# Real_Time_Clock.net
KiCad netlist of a schematic drawn in Altium Designer
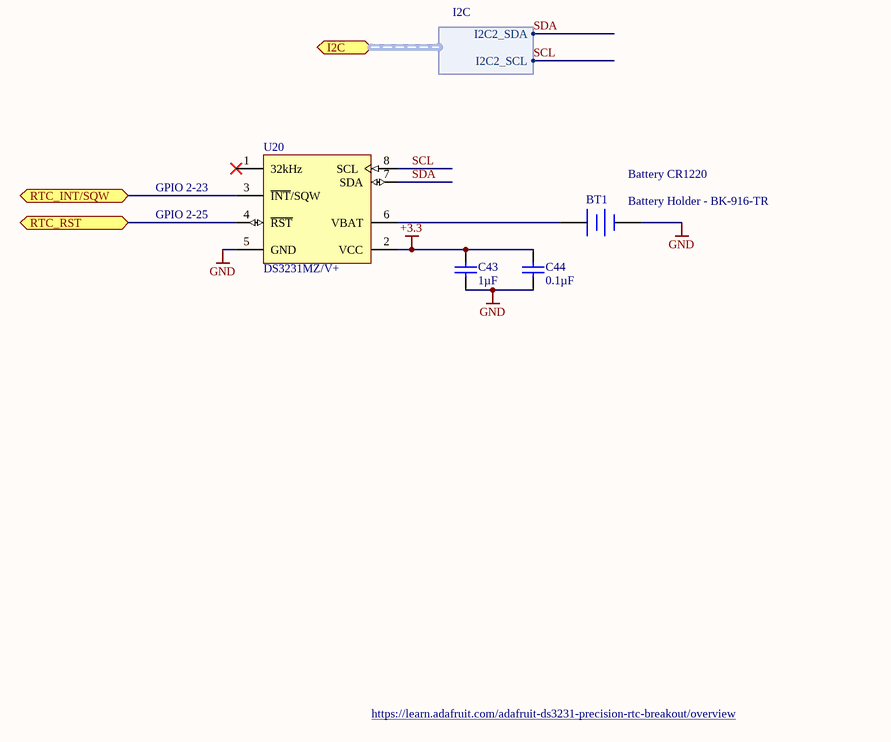
[diagram p0: Real Time Clock.SchDoc]

(export (version "E")
  (design (tool "Eeschema 10.0.6"))
  (components
    (comp (ref "BT1")
      (value "Battery Holder - BK-916-TR")
      (footprint "BK-916-TR")
      (description "CR1220, 1225 BATTERY RETAINER W/")
      (libsource (lib "Miscellaneous Devices") (part "Battery"))
    )
    (comp (ref "C43")
      (value "CAP 1uF 25V 0805(2012)")
      (footprint "CAPC0805(2012)100_M")
      (description "CAP 1uF 25V ±10% 0805 (2012 Metric) Thickness 1mm SMD")
      (fields
        (field (name "MANUFACTURER") "Murata Electronics North America")
        (field (name "MANUFACTURER PART NUMBER") "GRM21BR71E105KA99L")
        (field (name "CAPACITANCE") "1µF")
      )
      (libsource (lib "Altium Content Vault") (part "CMP-1036-04754-1"))
    )
    (comp (ref "C44")
      (value "CAP 100nF 25V 0805(2012)")
      (footprint "CAPC0805(2012)100_N")
      (description "CAP 100nF 25V -20% to +80% 0805 (2012 Metric) Thickness 1mm SMD")
      (fields
        (field (name "MANUFACTURER") "Murata Electronics North America")
        (field (name "MANUFACTURER PART NUMBER") "GRM21BR71E104KA01L")
        (field (name "CAPACITANCE") "0.1µF")
      )
      (libsource (lib "Altium Content Vault") (part "CMP-1036-04416-1"))
    )
    (comp (ref "U20")
      (value "DS3231MZ/V+")
      (footprint "S8MK+1_N")
      (libsource (lib "Altium Content Vault") (part "CMP-0254-00374-1"))
    )
  )
  (nets
    (net (code "2") (name "+3.3") (class "Default")
      (node (ref "C43") (pin "1") (pinfunction "1_1") (pintype "passive"))
      (node (ref "C44") (pin "1") (pinfunction "1_1") (pintype "passive"))
      (node (ref "U20") (pin "2") (pinfunction "VCC_2") (pintype "power_in"))
    )
    (net (code "3") (name "/RTC_INT{slash}SQW") (class "Default")
      (node (ref "U20") (pin "3") (pinfunction "~{INT}/SQW_3") (pintype "open_collector"))
    )
    (net (code "4") (name "/RTC_RST") (class "Default")
      (node (ref "U20") (pin "4") (pinfunction "~{RST}_4") (pintype "bidirectional"))
    )
    (net (code "5") (name "/SCL") (class "Default")
      (node (ref "U20") (pin "8") (pinfunction "SCL_8") (pintype "input"))
    )
    (net (code "6") (name "/SDA") (class "Default")
      (node (ref "U20") (pin "7") (pinfunction "SDA_7") (pintype "bidirectional"))
    )
    (net (code "8") (name "GND") (class "Default")
      (node (ref "BT1") (pin "2") (pinfunction "-_2") (pintype "passive"))
      (node (ref "C43") (pin "2") (pinfunction "2_2") (pintype "passive"))
      (node (ref "C44") (pin "2") (pinfunction "2_2") (pintype "passive"))
      (node (ref "U20") (pin "5") (pinfunction "GND_5") (pintype "power_in"))
    )
    (net (code "9") (name "Net-(BT1-+)") (class "Default")
      (node (ref "BT1") (pin "1") (pinfunction "+_1") (pintype "passive"))
      (node (ref "U20") (pin "6") (pinfunction "VBAT_6") (pintype "power_in"))
    )
    (net (code "10") (name "unconnected-(U20-32kHz-Pad1)") (class "Default")
      (node (ref "U20") (pin "1") (pinfunction "32kHz_1") (pintype "open_collector+no_connect"))
    )
  )
)
